# Wise-1530-v1_0.net
KiCad netlist of a schematic drawn in EAGLE
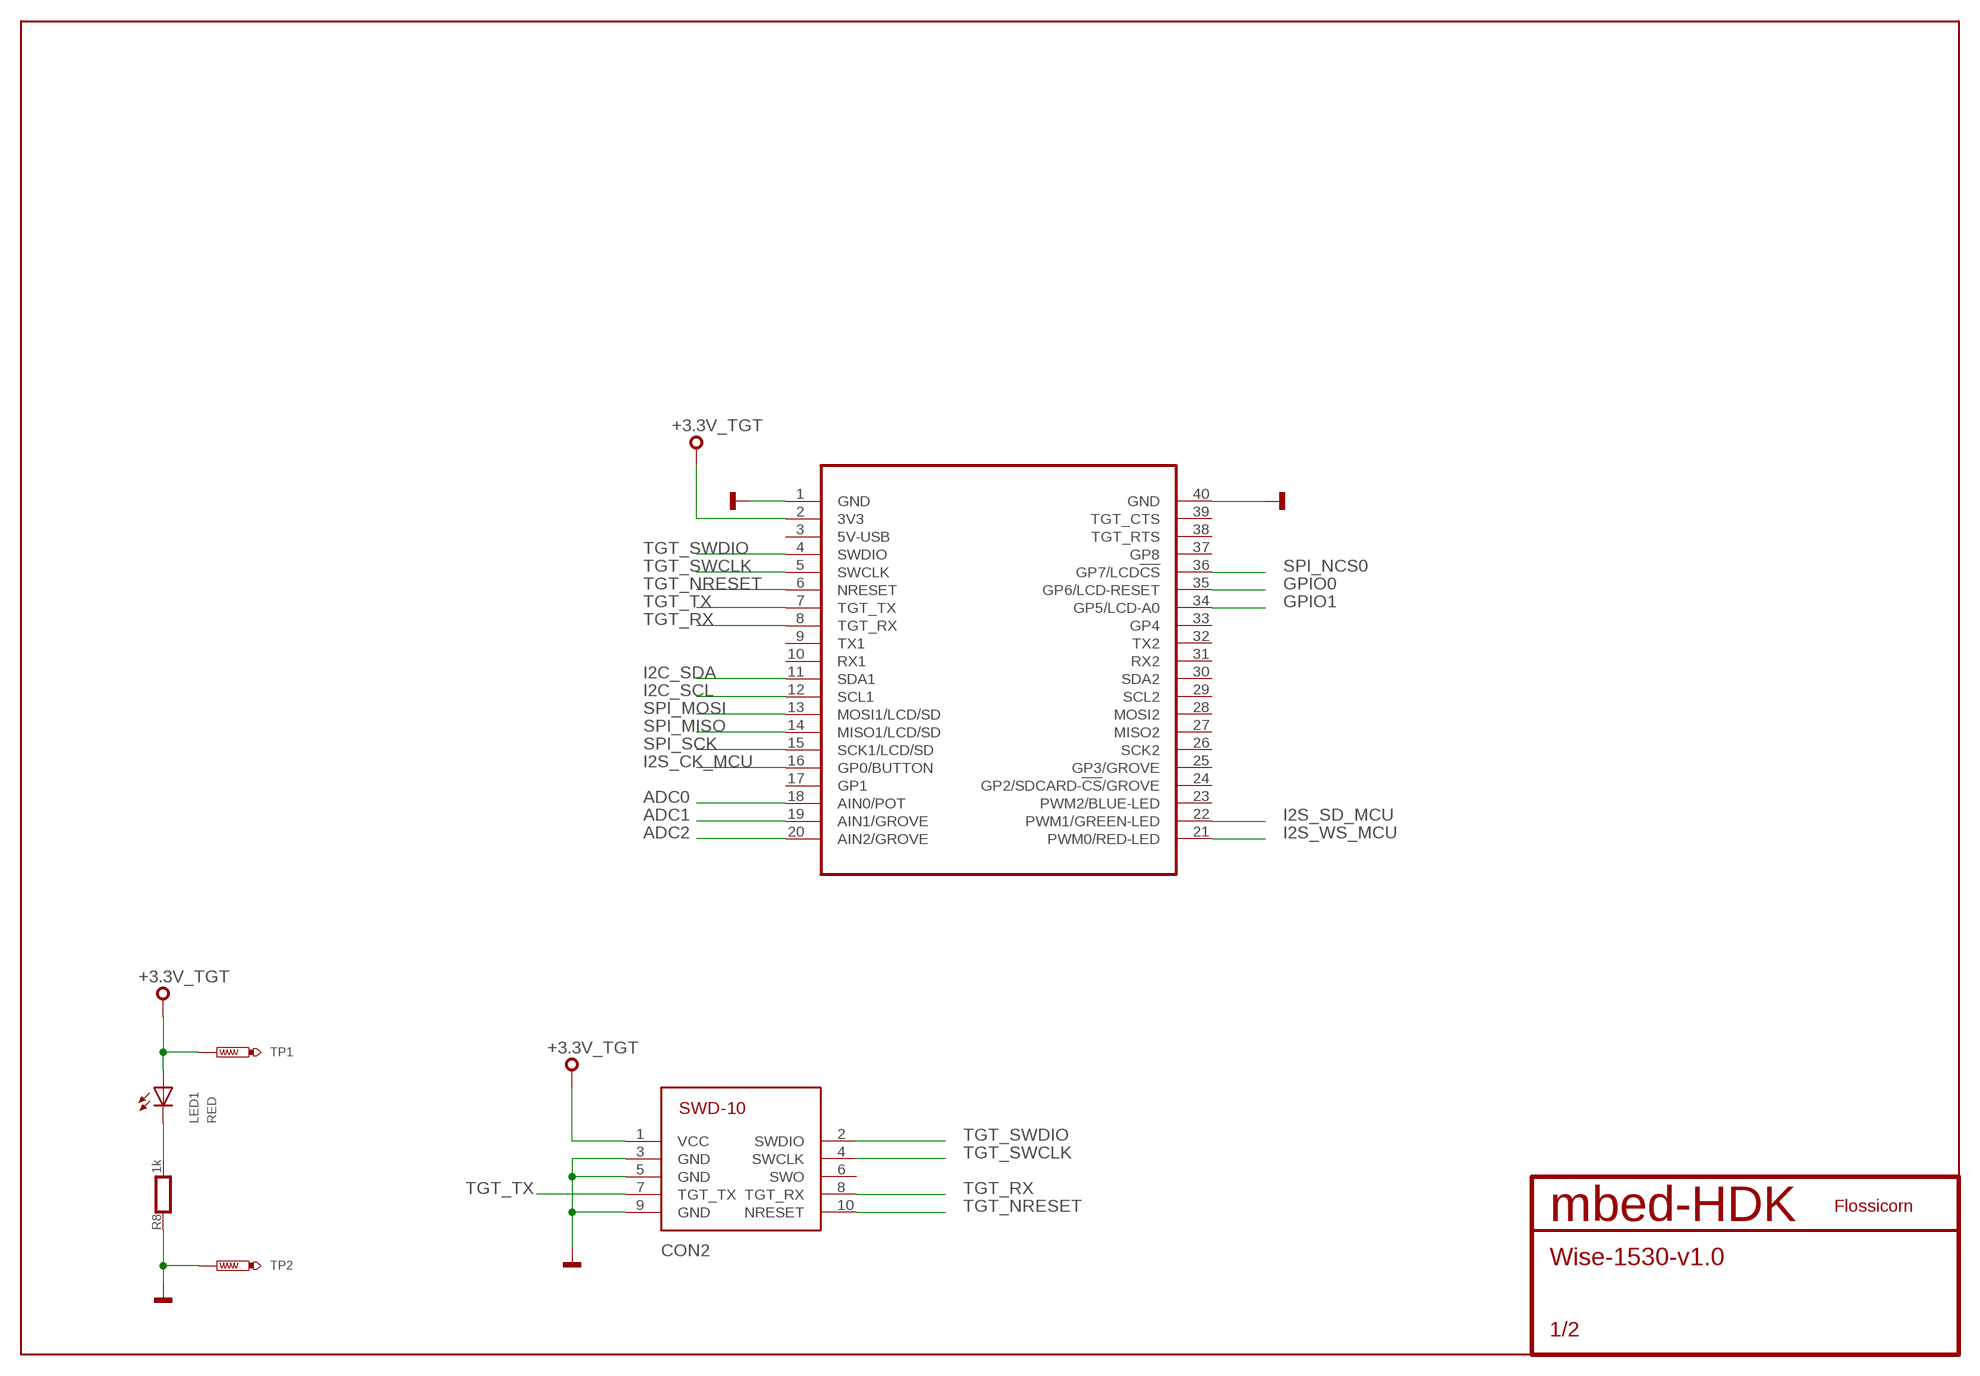
[diagram p0: schematic, sheet 1]
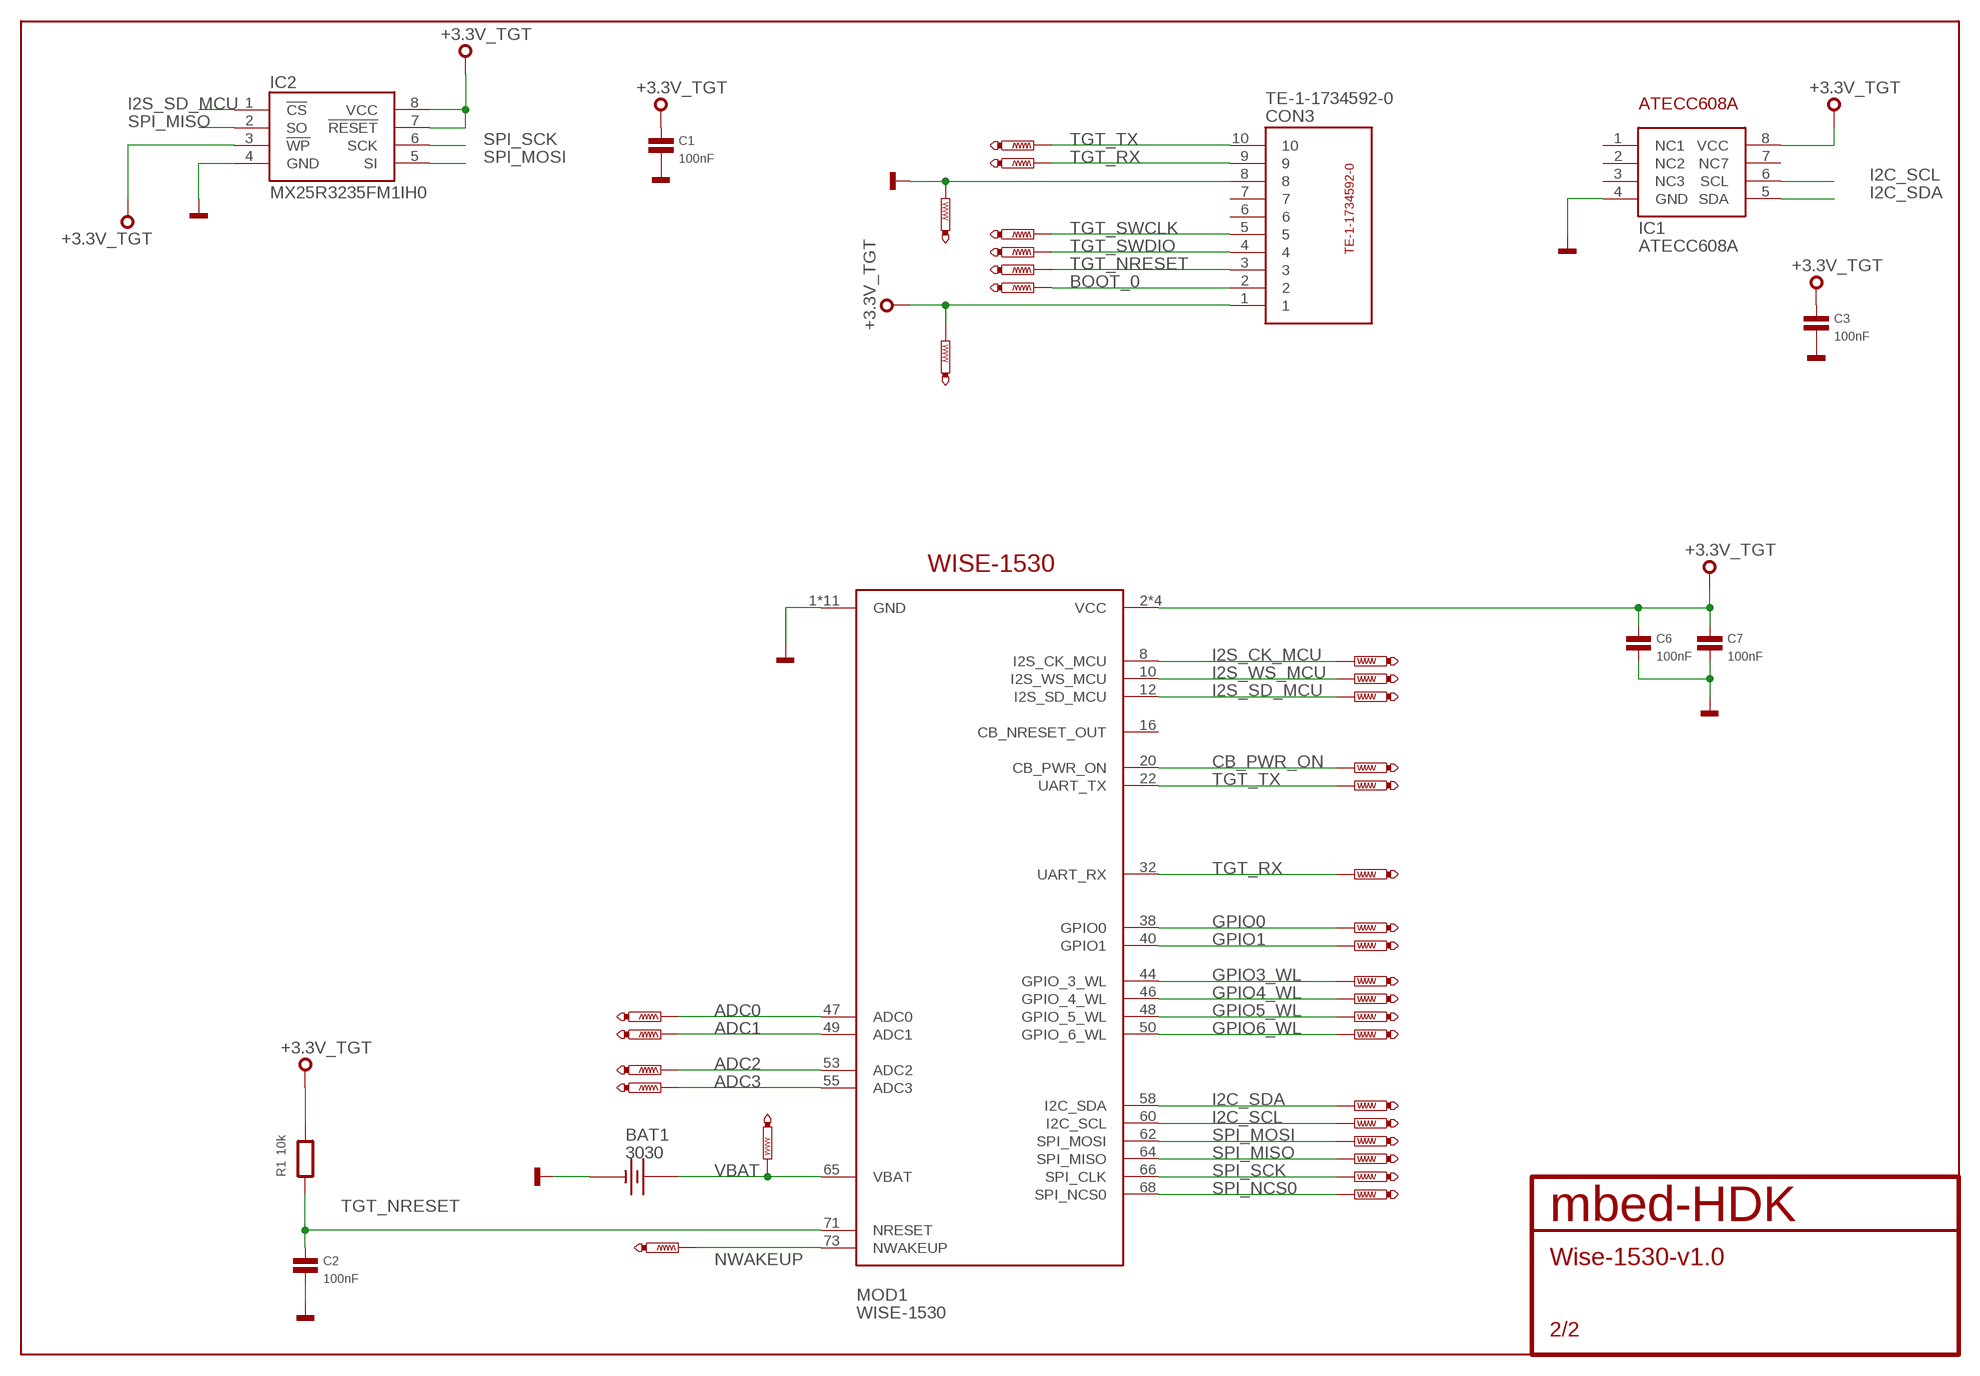
[diagram p1: schematic, sheet 2]

(export (version "E")
  (design (tool "Eeschema 10.0.6"))
  (components
    (comp (ref "BAT1")
      (value "3030")
      (footprint "eagle-import:3030")
      (fields (field (name "MF") "Keystone"))
      (libsource (lib "eagle-import") (part "3030"))
    )
    (comp (ref "C1")
      (value "100nF")
      (footprint "eagle-import:0603")
      (libsource (lib "eagle-import") (part "CAPACITOR0603"))
    )
    (comp (ref "C2")
      (value "100nF")
      (footprint "eagle-import:0603")
      (libsource (lib "eagle-import") (part "CAPACITOR0603"))
    )
    (comp (ref "C3")
      (value "100nF")
      (footprint "eagle-import:0603")
      (libsource (lib "eagle-import") (part "CAPACITOR0603"))
    )
    (comp (ref "C6")
      (value "100nF")
      (footprint "eagle-import:0603")
      (libsource (lib "eagle-import") (part "CAPACITOR0603"))
    )
    (comp (ref "C7")
      (value "100nF")
      (footprint "eagle-import:0603")
      (libsource (lib "eagle-import") (part "CAPACITOR0603"))
    )
    (comp (ref "CON3")
      (value "TE-1-1734592-0")
      (footprint "eagle-import:TE-1-1734592-0")
      (libsource (lib "eagle-import") (part "TE-1-1734592-0"))
    )
    (comp (ref "IC1")
      (value "ATECC608A")
      (footprint "eagle-import:SO8")
      (libsource (lib "eagle-import") (part "ATECC608A"))
    )
    (comp (ref "IC2")
      (value "MX25R3235FM1IH0")
      (footprint "eagle-import:SO8")
      (fields (field (name "MF") "Macronix"))
      (libsource (lib "eagle-import") (part "MX25R3235FM1IH0"))
    )
    (comp (ref "MOD1")
      (value "WISE-1530")
      (footprint "eagle-import:MDT420E02001")
      (libsource (lib "eagle-import") (part "WISE-1530"))
    )
    (comp (ref "R1")
      (value "10k")
      (footprint "eagle-import:0603")
      (libsource (lib "eagle-import") (part "RESISTOR0603"))
    )
    (comp (ref "TP3")
      (value "PTR1TP08R")
      (footprint "eagle-import:TP08R")
      (libsource (lib "eagle-import") (part "PTR1TP08R"))
    )
    (comp (ref "TP4")
      (value "PTR1TP08R")
      (footprint "eagle-import:TP08R")
      (libsource (lib "eagle-import") (part "PTR1TP08R"))
    )
    (comp (ref "TP5")
      (value "PTR1TP08R")
      (footprint "eagle-import:TP08R")
      (libsource (lib "eagle-import") (part "PTR1TP08R"))
    )
    (comp (ref "TP6")
      (value "PTR1TP08R")
      (footprint "eagle-import:TP08R")
      (libsource (lib "eagle-import") (part "PTR1TP08R"))
    )
    (comp (ref "TP7")
      (value "PTR1TP08R")
      (footprint "eagle-import:TP08R")
      (libsource (lib "eagle-import") (part "PTR1TP08R"))
    )
    (comp (ref "TP8")
      (value "PTR1TP08R")
      (footprint "eagle-import:TP08R")
      (libsource (lib "eagle-import") (part "PTR1TP08R"))
    )
    (comp (ref "TP9")
      (value "PTR1TP07R")
      (footprint "eagle-import:TP07R")
      (libsource (lib "eagle-import") (part "PTR1TP07R"))
    )
    (comp (ref "TP10")
      (value "PTR1TP07R")
      (footprint "eagle-import:TP07R")
      (libsource (lib "eagle-import") (part "PTR1TP07R"))
    )
    (comp (ref "TP11")
      (value "PTR1TP07R")
      (footprint "eagle-import:TP07R")
      (libsource (lib "eagle-import") (part "PTR1TP07R"))
    )
    (comp (ref "TP12")
      (value "PTR1TP08R")
      (footprint "eagle-import:TP08R")
      (libsource (lib "eagle-import") (part "PTR1TP08R"))
    )
    (comp (ref "TP13")
      (value "PTR1TP08R")
      (footprint "eagle-import:TP08R")
      (libsource (lib "eagle-import") (part "PTR1TP08R"))
    )
    (comp (ref "TP14")
      (value "PTR1TP07R")
      (footprint "eagle-import:TP07R")
      (libsource (lib "eagle-import") (part "PTR1TP07R"))
    )
    (comp (ref "TP15")
      (value "PTR1TP07R")
      (footprint "eagle-import:TP07R")
      (libsource (lib "eagle-import") (part "PTR1TP07R"))
    )
    (comp (ref "TP16")
      (value "PTR1TP07R")
      (footprint "eagle-import:TP07R")
      (libsource (lib "eagle-import") (part "PTR1TP07R"))
    )
    (comp (ref "TP17")
      (value "PTR1TP07R")
      (footprint "eagle-import:TP07R")
      (libsource (lib "eagle-import") (part "PTR1TP07R"))
    )
    (comp (ref "TP18")
      (value "PTR1TP07R")
      (footprint "eagle-import:TP07R")
      (libsource (lib "eagle-import") (part "PTR1TP07R"))
    )
    (comp (ref "TP19")
      (value "PTR1TP07R")
      (footprint "eagle-import:TP07R")
      (libsource (lib "eagle-import") (part "PTR1TP07R"))
    )
    (comp (ref "TP20")
      (value "PTR1TP07R")
      (footprint "eagle-import:TP07R")
      (libsource (lib "eagle-import") (part "PTR1TP07R"))
    )
    (comp (ref "TP21")
      (value "PTR1TP07R")
      (footprint "eagle-import:TP07R")
      (libsource (lib "eagle-import") (part "PTR1TP07R"))
    )
    (comp (ref "TP22")
      (value "PTR1TP07R")
      (footprint "eagle-import:TP07R")
      (libsource (lib "eagle-import") (part "PTR1TP07R"))
    )
    (comp (ref "TP23")
      (value "PTR1TP07R")
      (footprint "eagle-import:TP07R")
      (libsource (lib "eagle-import") (part "PTR1TP07R"))
    )
    (comp (ref "TP24")
      (value "PTR1TP07R")
      (footprint "eagle-import:TP07R")
      (libsource (lib "eagle-import") (part "PTR1TP07R"))
    )
    (comp (ref "TP25")
      (value "PTR1TP07R")
      (footprint "eagle-import:TP07R")
      (libsource (lib "eagle-import") (part "PTR1TP07R"))
    )
    (comp (ref "TP26")
      (value "PTR1TP07R")
      (footprint "eagle-import:TP07R")
      (libsource (lib "eagle-import") (part "PTR1TP07R"))
    )
    (comp (ref "TP27")
      (value "PTR1TP07R")
      (footprint "eagle-import:TP07R")
      (libsource (lib "eagle-import") (part "PTR1TP07R"))
    )
    (comp (ref "TP28")
      (value "PTR1TP07R")
      (footprint "eagle-import:TP07R")
      (libsource (lib "eagle-import") (part "PTR1TP07R"))
    )
    (comp (ref "TP29")
      (value "PTR1TP07R")
      (footprint "eagle-import:TP07R")
      (libsource (lib "eagle-import") (part "PTR1TP07R"))
    )
    (comp (ref "TP30")
      (value "PTR1TP07R")
      (footprint "eagle-import:TP07R")
      (libsource (lib "eagle-import") (part "PTR1TP07R"))
    )
    (comp (ref "TP31")
      (value "PTR1TP07R")
      (footprint "eagle-import:TP07R")
      (libsource (lib "eagle-import") (part "PTR1TP07R"))
    )
    (comp (ref "TP32")
      (value "PTR1TP07R")
      (footprint "eagle-import:TP07R")
      (libsource (lib "eagle-import") (part "PTR1TP07R"))
    )
    (comp (ref "TP33")
      (value "PTR1TP07R")
      (footprint "eagle-import:TP07R")
      (libsource (lib "eagle-import") (part "PTR1TP07R"))
    )
    (comp (ref "TP34")
      (value "PTR1TP07R")
      (footprint "eagle-import:TP07R")
      (libsource (lib "eagle-import") (part "PTR1TP07R"))
    )
    (comp (ref "CON2")
      (value "SWD-10/TC2050_SMD")
      (footprint "eagle-import:FTSH-105-02")
      (libsource (lib "eagle-import") (part "SWD-10/TC2050_SMD"))
    )
    (comp (ref "LED1")
      (value "RED")
      (footprint "eagle-import:CHIPLED_0603")
      (fields (field (name "MF") "Wurth Electronics Inc"))
      (libsource (lib "eagle-import") (part "SMD_LED0603"))
    )
    (comp (ref "MOD2")
      (value "MODULE_DAUGHTER")
      (footprint "eagle-import:MODULE_DAUGHTER")
      (libsource (lib "eagle-import") (part "MODULE_DAUGHTER"))
    )
    (comp (ref "R8")
      (value "1k")
      (footprint "eagle-import:0603")
      (libsource (lib "eagle-import") (part "RESISTOR0603"))
    )
    (comp (ref "SS1")
      (value "FLOSSICORN0.25")
      (footprint "eagle-import:FLOSSICORN-0.25")
      (libsource (lib "eagle-import") (part "FLOSSICORN0.25"))
    )
    (comp (ref "TP1")
      (value "TEST-POINT-50R-PTH")
      (footprint "eagle-import:TP50-PTH")
      (libsource (lib "eagle-import") (part "TEST-POINT-50R-PTH"))
    )
    (comp (ref "TP2")
      (value "TEST-POINT-50R-PTH")
      (footprint "eagle-import:TP50-PTH")
      (libsource (lib "eagle-import") (part "TEST-POINT-50R-PTH"))
    )
  )
  (nets
    (net (code "1") (name "+3.3V_TGT") (class "Default")
      (node (ref "C1") (pin "1") (pinfunction "P$1_1") (pintype "passive"))
      (node (ref "C3") (pin "1") (pinfunction "P$1_1") (pintype "passive"))
      (node (ref "C6") (pin "1") (pinfunction "P$1_1") (pintype "passive"))
      (node (ref "C7") (pin "1") (pinfunction "P$1_1") (pintype "passive"))
      (node (ref "CON2") (pin "1") (pinfunction "VCC_1") (pintype "bidirectional"))
      (node (ref "CON3") (pin "1") (pinfunction "1_1") (pintype "bidirectional"))
      (node (ref "IC1") (pin "8") (pinfunction "VCC_8") (pintype "bidirectional"))
      (node (ref "IC2") (pin "3") (pinfunction "~{WP}_3") (pintype "bidirectional"))
      (node (ref "IC2") (pin "7") (pinfunction "~{RESET}_7") (pintype "bidirectional"))
      (node (ref "IC2") (pin "8") (pinfunction "VCC_8") (pintype "bidirectional"))
      (node (ref "LED1") (pin "A") (pinfunction "A_A") (pintype "passive"))
      (node (ref "MOD1") (pin "2") (pinfunction "VCC_2") (pintype "bidirectional"))
      (node (ref "MOD1") (pin "4") (pinfunction "VCC_4") (pintype "bidirectional"))
      (node (ref "MOD1") (pin "72") (pinfunction "VCC_72") (pintype "bidirectional"))
      (node (ref "MOD1") (pin "74") (pinfunction "VCC_74") (pintype "bidirectional"))
      (node (ref "MOD2") (pin "2") (pinfunction "3V3_2") (pintype "bidirectional"))
      (node (ref "R1") (pin "2") (pinfunction "P$2_2") (pintype "passive"))
      (node (ref "TP1") (pin "TP") (pinfunction "TP_TP") (pintype "input"))
      (node (ref "TP12") (pin "TP") (pinfunction "TP_TP") (pintype "input"))
    )
    (net (code "2") (name "ADC0") (class "Default")
      (node (ref "MOD1") (pin "47") (pinfunction "ADC0_47") (pintype "bidirectional"))
      (node (ref "MOD2") (pin "18") (pinfunction "AIN0/POT_18") (pintype "bidirectional"))
      (node (ref "TP29") (pin "TP") (pinfunction "TP_TP") (pintype "input"))
    )
    (net (code "3") (name "ADC1") (class "Default")
      (node (ref "MOD1") (pin "49") (pinfunction "ADC1_49") (pintype "bidirectional"))
      (node (ref "MOD2") (pin "19") (pinfunction "AIN1/GROVE_19") (pintype "bidirectional"))
      (node (ref "TP30") (pin "TP") (pinfunction "TP_TP") (pintype "input"))
    )
    (net (code "4") (name "ADC2") (class "Default")
      (node (ref "MOD1") (pin "53") (pinfunction "ADC2_53") (pintype "bidirectional"))
      (node (ref "MOD2") (pin "20") (pinfunction "AIN2/GROVE_20") (pintype "bidirectional"))
      (node (ref "TP31") (pin "TP") (pinfunction "TP_TP") (pintype "input"))
    )
    (net (code "5") (name "ADC3") (class "Default")
      (node (ref "MOD1") (pin "55") (pinfunction "ADC3_55") (pintype "bidirectional"))
      (node (ref "TP32") (pin "TP") (pinfunction "TP_TP") (pintype "input"))
    )
    (net (code "6") (name "BOOT_0") (class "Default")
      (node (ref "CON3") (pin "2") (pinfunction "2_2") (pintype "bidirectional"))
      (node (ref "TP8") (pin "TP") (pinfunction "TP_TP") (pintype "input"))
    )
    (net (code "7") (name "CB_PWR_ON") (class "Default")
      (node (ref "MOD1") (pin "20") (pinfunction "CB_PWR_ON_20") (pintype "bidirectional"))
      (node (ref "TP14") (pin "TP") (pinfunction "TP_TP") (pintype "input"))
    )
    (net (code "8") (name "GND") (class "Default")
      (node (ref "BAT1") (pin "-") (pinfunction "-_-") (pintype "bidirectional"))
      (node (ref "C1") (pin "2") (pinfunction "P$2_2") (pintype "passive"))
      (node (ref "C2") (pin "2") (pinfunction "P$2_2") (pintype "passive"))
      (node (ref "C3") (pin "2") (pinfunction "P$2_2") (pintype "passive"))
      (node (ref "C6") (pin "2") (pinfunction "P$2_2") (pintype "passive"))
      (node (ref "C7") (pin "2") (pinfunction "P$2_2") (pintype "passive"))
      (node (ref "CON2") (pin "3") (pinfunction "GND_3") (pintype "bidirectional"))
      (node (ref "CON2") (pin "5") (pinfunction "GND_5") (pintype "bidirectional"))
      (node (ref "CON2") (pin "9") (pinfunction "GND_9") (pintype "bidirectional"))
      (node (ref "CON3") (pin "8") (pinfunction "8_8") (pintype "bidirectional"))
      (node (ref "IC1") (pin "4") (pinfunction "GND_4") (pintype "bidirectional"))
      (node (ref "IC2") (pin "4") (pinfunction "GND_4") (pintype "bidirectional"))
      (node (ref "MOD1") (pin "1") (pinfunction "GND_1") (pintype "bidirectional"))
      (node (ref "MOD1") (pin "18") (pinfunction "GND_18") (pintype "bidirectional"))
      (node (ref "MOD1") (pin "33") (pinfunction "GND_33") (pintype "bidirectional"))
      (node (ref "MOD1") (pin "39") (pinfunction "GND_39") (pintype "bidirectional"))
      (node (ref "MOD1") (pin "45") (pinfunction "GND_45") (pintype "bidirectional"))
      (node (ref "MOD1") (pin "51") (pinfunction "GND_51") (pintype "bidirectional"))
      (node (ref "MOD1") (pin "57") (pinfunction "GND_57") (pintype "bidirectional"))
      (node (ref "MOD1") (pin "63") (pinfunction "GND_63") (pintype "bidirectional"))
      (node (ref "MOD1") (pin "69") (pinfunction "GND_69") (pintype "bidirectional"))
      (node (ref "MOD1") (pin "7") (pinfunction "GND_7") (pintype "bidirectional"))
      (node (ref "MOD1") (pin "75") (pinfunction "GND_75") (pintype "bidirectional"))
      (node (ref "MOD2") (pin "1") (pinfunction "GND_1") (pintype "bidirectional"))
      (node (ref "MOD2") (pin "40") (pinfunction "GND_40") (pintype "bidirectional"))
      (node (ref "R8") (pin "1") (pinfunction "P$1_1") (pintype "passive"))
      (node (ref "TP13") (pin "TP") (pinfunction "TP_TP") (pintype "input"))
      (node (ref "TP2") (pin "TP") (pinfunction "TP_TP") (pintype "input"))
    )
    (net (code "9") (name "GPIO0") (class "Default")
      (node (ref "MOD1") (pin "38") (pinfunction "GPIO0_38") (pintype "bidirectional"))
      (node (ref "MOD2") (pin "35") (pinfunction "GP6/LCD-RESET_35") (pintype "bidirectional"))
      (node (ref "TP27") (pin "TP") (pinfunction "TP_TP") (pintype "input"))
    )
    (net (code "10") (name "GPIO1") (class "Default")
      (node (ref "MOD1") (pin "40") (pinfunction "GPIO1_40") (pintype "bidirectional"))
      (node (ref "MOD2") (pin "34") (pinfunction "GP5/LCD-A0_34") (pintype "bidirectional"))
      (node (ref "TP26") (pin "TP") (pinfunction "TP_TP") (pintype "input"))
    )
    (net (code "11") (name "GPIO3_WL") (class "Default")
      (node (ref "MOD1") (pin "44") (pinfunction "GPIO_3_WL_44") (pintype "bidirectional"))
      (node (ref "TP25") (pin "TP") (pinfunction "TP_TP") (pintype "input"))
    )
    (net (code "12") (name "GPIO4_WL") (class "Default")
      (node (ref "MOD1") (pin "46") (pinfunction "GPIO_4_WL_46") (pintype "bidirectional"))
      (node (ref "TP24") (pin "TP") (pinfunction "TP_TP") (pintype "input"))
    )
    (net (code "13") (name "GPIO5_WL") (class "Default")
      (node (ref "MOD1") (pin "48") (pinfunction "GPIO_5_WL_48") (pintype "bidirectional"))
      (node (ref "TP23") (pin "TP") (pinfunction "TP_TP") (pintype "input"))
    )
    (net (code "14") (name "GPIO6_WL") (class "Default")
      (node (ref "MOD1") (pin "50") (pinfunction "GPIO_6_WL_50") (pintype "bidirectional"))
      (node (ref "TP22") (pin "TP") (pinfunction "TP_TP") (pintype "input"))
    )
    (net (code "15") (name "I2C_SCL") (class "Default")
      (node (ref "IC1") (pin "6") (pinfunction "SCL_6") (pintype "bidirectional"))
      (node (ref "MOD1") (pin "60") (pinfunction "I2C_SCL_60") (pintype "bidirectional"))
      (node (ref "MOD2") (pin "12") (pinfunction "SCL1_12") (pintype "bidirectional"))
      (node (ref "TP20") (pin "TP") (pinfunction "TP_TP") (pintype "input"))
    )
    (net (code "16") (name "I2C_SDA") (class "Default")
      (node (ref "IC1") (pin "5") (pinfunction "SDA_5") (pintype "bidirectional"))
      (node (ref "MOD1") (pin "58") (pinfunction "I2C_SDA_58") (pintype "bidirectional"))
      (node (ref "MOD2") (pin "11") (pinfunction "SDA1_11") (pintype "bidirectional"))
      (node (ref "TP21") (pin "TP") (pinfunction "TP_TP") (pintype "input"))
    )
    (net (code "17") (name "I2S_CK_MCU") (class "Default")
      (node (ref "MOD1") (pin "8") (pinfunction "I2S_CK_MCU_8") (pintype "bidirectional"))
      (node (ref "MOD2") (pin "16") (pinfunction "GP0/BUTTON_16") (pintype "bidirectional"))
      (node (ref "TP9") (pin "TP") (pinfunction "TP_TP") (pintype "input"))
    )
    (net (code "18") (name "I2S_SD_MCU") (class "Default")
      (node (ref "IC2") (pin "1") (pinfunction "~{CS}_1") (pintype "bidirectional"))
      (node (ref "MOD1") (pin "12") (pinfunction "I2S_SD_MCU_12") (pintype "bidirectional"))
      (node (ref "MOD2") (pin "22") (pinfunction "PWM1/GREEN-LED_22") (pintype "bidirectional"))
      (node (ref "TP11") (pin "TP") (pinfunction "TP_TP") (pintype "input"))
    )
    (net (code "19") (name "I2S_WS_MCU") (class "Default")
      (node (ref "MOD1") (pin "10") (pinfunction "I2S_WS_MCU_10") (pintype "bidirectional"))
      (node (ref "MOD2") (pin "21") (pinfunction "PWM0/RED-LED_21") (pintype "bidirectional"))
      (node (ref "TP10") (pin "TP") (pinfunction "TP_TP") (pintype "input"))
    )
    (net (code "20") (name "NWAKEUP") (class "Default")
      (node (ref "MOD1") (pin "73") (pinfunction "NWAKEUP_73") (pintype "bidirectional"))
      (node (ref "TP34") (pin "TP") (pinfunction "TP_TP") (pintype "input"))
    )
    (net (code "21") (name "Net-(R8-P$2)") (class "Default")
      (node (ref "LED1") (pin "C") (pinfunction "C_C") (pintype "passive"))
      (node (ref "R8") (pin "2") (pinfunction "P$2_2") (pintype "passive"))
    )
    (net (code "22") (name "SPI_MISO") (class "Default")
      (node (ref "IC2") (pin "2") (pinfunction "SO_2") (pintype "bidirectional"))
      (node (ref "MOD1") (pin "64") (pinfunction "SPI_MISO_64") (pintype "bidirectional"))
      (node (ref "MOD2") (pin "14") (pinfunction "MISO1/LCD/SD_14") (pintype "bidirectional"))
      (node (ref "TP18") (pin "TP") (pinfunction "TP_TP") (pintype "input"))
    )
    (net (code "23") (name "SPI_MOSI") (class "Default")
      (node (ref "IC2") (pin "5") (pinfunction "SI_5") (pintype "bidirectional"))
      (node (ref "MOD1") (pin "62") (pinfunction "SPI_MOSI_62") (pintype "bidirectional"))
      (node (ref "MOD2") (pin "13") (pinfunction "MOSI1/LCD/SD_13") (pintype "bidirectional"))
      (node (ref "TP19") (pin "TP") (pinfunction "TP_TP") (pintype "input"))
    )
    (net (code "24") (name "SPI_NCS0") (class "Default")
      (node (ref "MOD1") (pin "68") (pinfunction "SPI_NCS0_68") (pintype "bidirectional"))
      (node (ref "MOD2") (pin "36") (pinfunction "GP7/LCD~{CS}_36") (pintype "bidirectional"))
      (node (ref "TP16") (pin "TP") (pinfunction "TP_TP") (pintype "input"))
    )
    (net (code "25") (name "SPI_SCK") (class "Default")
      (node (ref "IC2") (pin "6") (pinfunction "SCK_6") (pintype "bidirectional"))
      (node (ref "MOD1") (pin "66") (pinfunction "SPI_CLK_66") (pintype "bidirectional"))
      (node (ref "MOD2") (pin "15") (pinfunction "SCK1/LCD/SD_15") (pintype "bidirectional"))
      (node (ref "TP17") (pin "TP") (pinfunction "TP_TP") (pintype "input"))
    )
    (net (code "26") (name "TGT_NRESET") (class "Default")
      (node (ref "C2") (pin "1") (pinfunction "P$1_1") (pintype "passive"))
      (node (ref "CON2") (pin "10") (pinfunction "NRESET_10") (pintype "bidirectional"))
      (node (ref "CON3") (pin "3") (pinfunction "3_3") (pintype "bidirectional"))
      (node (ref "MOD1") (pin "71") (pinfunction "NRESET_71") (pintype "bidirectional"))
      (node (ref "MOD2") (pin "6") (pinfunction "NRESET_6") (pintype "bidirectional"))
      (node (ref "R1") (pin "1") (pinfunction "P$1_1") (pintype "passive"))
      (node (ref "TP5") (pin "TP") (pinfunction "TP_TP") (pintype "input"))
    )
    (net (code "27") (name "TGT_RX") (class "Default")
      (node (ref "CON2") (pin "8") (pinfunction "TGT_RX_8") (pintype "bidirectional"))
      (node (ref "CON3") (pin "9") (pinfunction "9_9") (pintype "bidirectional"))
      (node (ref "MOD1") (pin "32") (pinfunction "UART_RX_32") (pintype "bidirectional"))
      (node (ref "MOD2") (pin "8") (pinfunction "TGT_RX_8") (pintype "bidirectional"))
      (node (ref "TP28") (pin "TP") (pinfunction "TP_TP") (pintype "input"))
      (node (ref "TP6") (pin "TP") (pinfunction "TP_TP") (pintype "input"))
    )
    (net (code "28") (name "TGT_SWCLK") (class "Default")
      (node (ref "CON2") (pin "4") (pinfunction "SWCLK_4") (pintype "bidirectional"))
      (node (ref "CON3") (pin "5") (pinfunction "5_5") (pintype "bidirectional"))
      (node (ref "MOD2") (pin "5") (pinfunction "SWCLK_5") (pintype "bidirectional"))
      (node (ref "TP3") (pin "TP") (pinfunction "TP_TP") (pintype "input"))
    )
    (net (code "29") (name "TGT_SWDIO") (class "Default")
      (node (ref "CON2") (pin "2") (pinfunction "SWDIO_2") (pintype "bidirectional"))
      (node (ref "CON3") (pin "4") (pinfunction "4_4") (pintype "bidirectional"))
      (node (ref "MOD2") (pin "4") (pinfunction "SWDIO_4") (pintype "bidirectional"))
      (node (ref "TP4") (pin "TP") (pinfunction "TP_TP") (pintype "input"))
    )
    (net (code "30") (name "TGT_TX") (class "Default")
      (node (ref "CON2") (pin "7") (pinfunction "TGT_TX_7") (pintype "bidirectional"))
      (node (ref "CON3") (pin "10") (pinfunction "10_10") (pintype "bidirectional"))
      (node (ref "MOD1") (pin "22") (pinfunction "UART_TX_22") (pintype "bidirectional"))
      (node (ref "MOD2") (pin "7") (pinfunction "TGT_TX_7") (pintype "bidirectional"))
      (node (ref "TP15") (pin "TP") (pinfunction "TP_TP") (pintype "input"))
      (node (ref "TP7") (pin "TP") (pinfunction "TP_TP") (pintype "input"))
    )
    (net (code "31") (name "VBAT") (class "Default")
      (node (ref "BAT1") (pin "+1") (pinfunction "+_+1") (pintype "bidirectional"))
      (node (ref "BAT1") (pin "+2") (pinfunction "+_+2") (pintype "bidirectional"))
      (node (ref "MOD1") (pin "65") (pinfunction "VBAT_65") (pintype "bidirectional"))
      (node (ref "TP33") (pin "TP") (pinfunction "TP_TP") (pintype "input"))
    )
    (net (code "32") (name "unconnected-(CON2-SWO-Pad6)") (class "Default")
      (node (ref "CON2") (pin "6") (pinfunction "SWO_6") (pintype "bidirectional"))
    )
    (net (code "33") (name "unconnected-(CON3-Pad6)") (class "Default")
      (node (ref "CON3") (pin "6") (pinfunction "6_6") (pintype "bidirectional"))
    )
    (net (code "34") (name "unconnected-(CON3-Pad7)") (class "Default")
      (node (ref "CON3") (pin "7") (pinfunction "7_7") (pintype "bidirectional"))
    )
    (net (code "35") (name "unconnected-(IC1-NC1-Pad1)") (class "Default")
      (node (ref "IC1") (pin "1") (pinfunction "NC1_1") (pintype "bidirectional"))
    )
    (net (code "36") (name "unconnected-(IC1-NC2-Pad2)") (class "Default")
      (node (ref "IC1") (pin "2") (pinfunction "NC2_2") (pintype "bidirectional"))
    )
    (net (code "37") (name "unconnected-(IC1-NC3-Pad3)") (class "Default")
      (node (ref "IC1") (pin "3") (pinfunction "NC3_3") (pintype "bidirectional"))
    )
    (net (code "38") (name "unconnected-(IC1-NC7-Pad7)") (class "Default")
      (node (ref "IC1") (pin "7") (pinfunction "NC7_7") (pintype "bidirectional"))
    )
    (net (code "39") (name "unconnected-(MOD1-CB_NRESET_OUT-Pad16)") (class "Default")
      (node (ref "MOD1") (pin "16") (pinfunction "CB_NRESET_OUT_16") (pintype "bidirectional"))
    )
    (net (code "40") (name "unconnected-(MOD2-5V-USB-Pad3)") (class "Default")
      (node (ref "MOD2") (pin "3") (pinfunction "5V-USB_3") (pintype "bidirectional"))
    )
    (net (code "41") (name "unconnected-(MOD2-GP1-Pad17)") (class "Default")
      (node (ref "MOD2") (pin "17") (pinfunction "GP1_17") (pintype "bidirectional"))
    )
    (net (code "42") (name "unconnected-(MOD2-GP2{slash}SDCARD-~{CS}{slash}GROVE-Pad24)") (class "Default")
      (node (ref "MOD2") (pin "24") (pinfunction "GP2/SDCARD-~{CS}/GROVE_24") (pintype "bidirectional"))
    )
    (net (code "43") (name "unconnected-(MOD2-GP3{slash}GROVE-Pad25)") (class "Default")
      (node (ref "MOD2") (pin "25") (pinfunction "GP3/GROVE_25") (pintype "bidirectional"))
    )
    (net (code "44") (name "unconnected-(MOD2-GP4-Pad33)") (class "Default")
      (node (ref "MOD2") (pin "33") (pinfunction "GP4_33") (pintype "bidirectional"))
    )
    (net (code "45") (name "unconnected-(MOD2-GP8-Pad37)") (class "Default")
      (node (ref "MOD2") (pin "37") (pinfunction "GP8_37") (pintype "bidirectional"))
    )
    (net (code "46") (name "unconnected-(MOD2-MISO2-Pad27)") (class "Default")
      (node (ref "MOD2") (pin "27") (pinfunction "MISO2_27") (pintype "bidirectional"))
    )
    (net (code "47") (name "unconnected-(MOD2-MOSI2-Pad28)") (class "Default")
      (node (ref "MOD2") (pin "28") (pinfunction "MOSI2_28") (pintype "bidirectional"))
    )
    (net (code "48") (name "unconnected-(MOD2-PWM2{slash}BLUE-LED-Pad23)") (class "Default")
      (node (ref "MOD2") (pin "23") (pinfunction "PWM2/BLUE-LED_23") (pintype "bidirectional"))
    )
    (net (code "49") (name "unconnected-(MOD2-RX1-Pad10)") (class "Default")
      (node (ref "MOD2") (pin "10") (pinfunction "RX1_10") (pintype "bidirectional"))
    )
    (net (code "50") (name "unconnected-(MOD2-RX2-Pad31)") (class "Default")
      (node (ref "MOD2") (pin "31") (pinfunction "RX2_31") (pintype "bidirectional"))
    )
    (net (code "51") (name "unconnected-(MOD2-SCK2-Pad26)") (class "Default")
      (node (ref "MOD2") (pin "26") (pinfunction "SCK2_26") (pintype "bidirectional"))
    )
    (net (code "52") (name "unconnected-(MOD2-SCL2-Pad29)") (class "Default")
      (node (ref "MOD2") (pin "29") (pinfunction "SCL2_29") (pintype "bidirectional"))
    )
    (net (code "53") (name "unconnected-(MOD2-SDA2-Pad30)") (class "Default")
      (node (ref "MOD2") (pin "30") (pinfunction "SDA2_30") (pintype "bidirectional"))
    )
    (net (code "54") (name "unconnected-(MOD2-TGT_CTS-Pad39)") (class "Default")
      (node (ref "MOD2") (pin "39") (pinfunction "TGT_CTS_39") (pintype "bidirectional"))
    )
    (net (code "55") (name "unconnected-(MOD2-TGT_RTS-Pad38)") (class "Default")
      (node (ref "MOD2") (pin "38") (pinfunction "TGT_RTS_38") (pintype "bidirectional"))
    )
    (net (code "56") (name "unconnected-(MOD2-TX1-Pad9)") (class "Default")
      (node (ref "MOD2") (pin "9") (pinfunction "TX1_9") (pintype "bidirectional"))
    )
    (net (code "57") (name "unconnected-(MOD2-TX2-Pad32)") (class "Default")
      (node (ref "MOD2") (pin "32") (pinfunction "TX2_32") (pintype "bidirectional"))
    )
  )
)
